# energy-harvesting-demoboard_v11.net
KiCad netlist of a schematic drawn in EAGLE
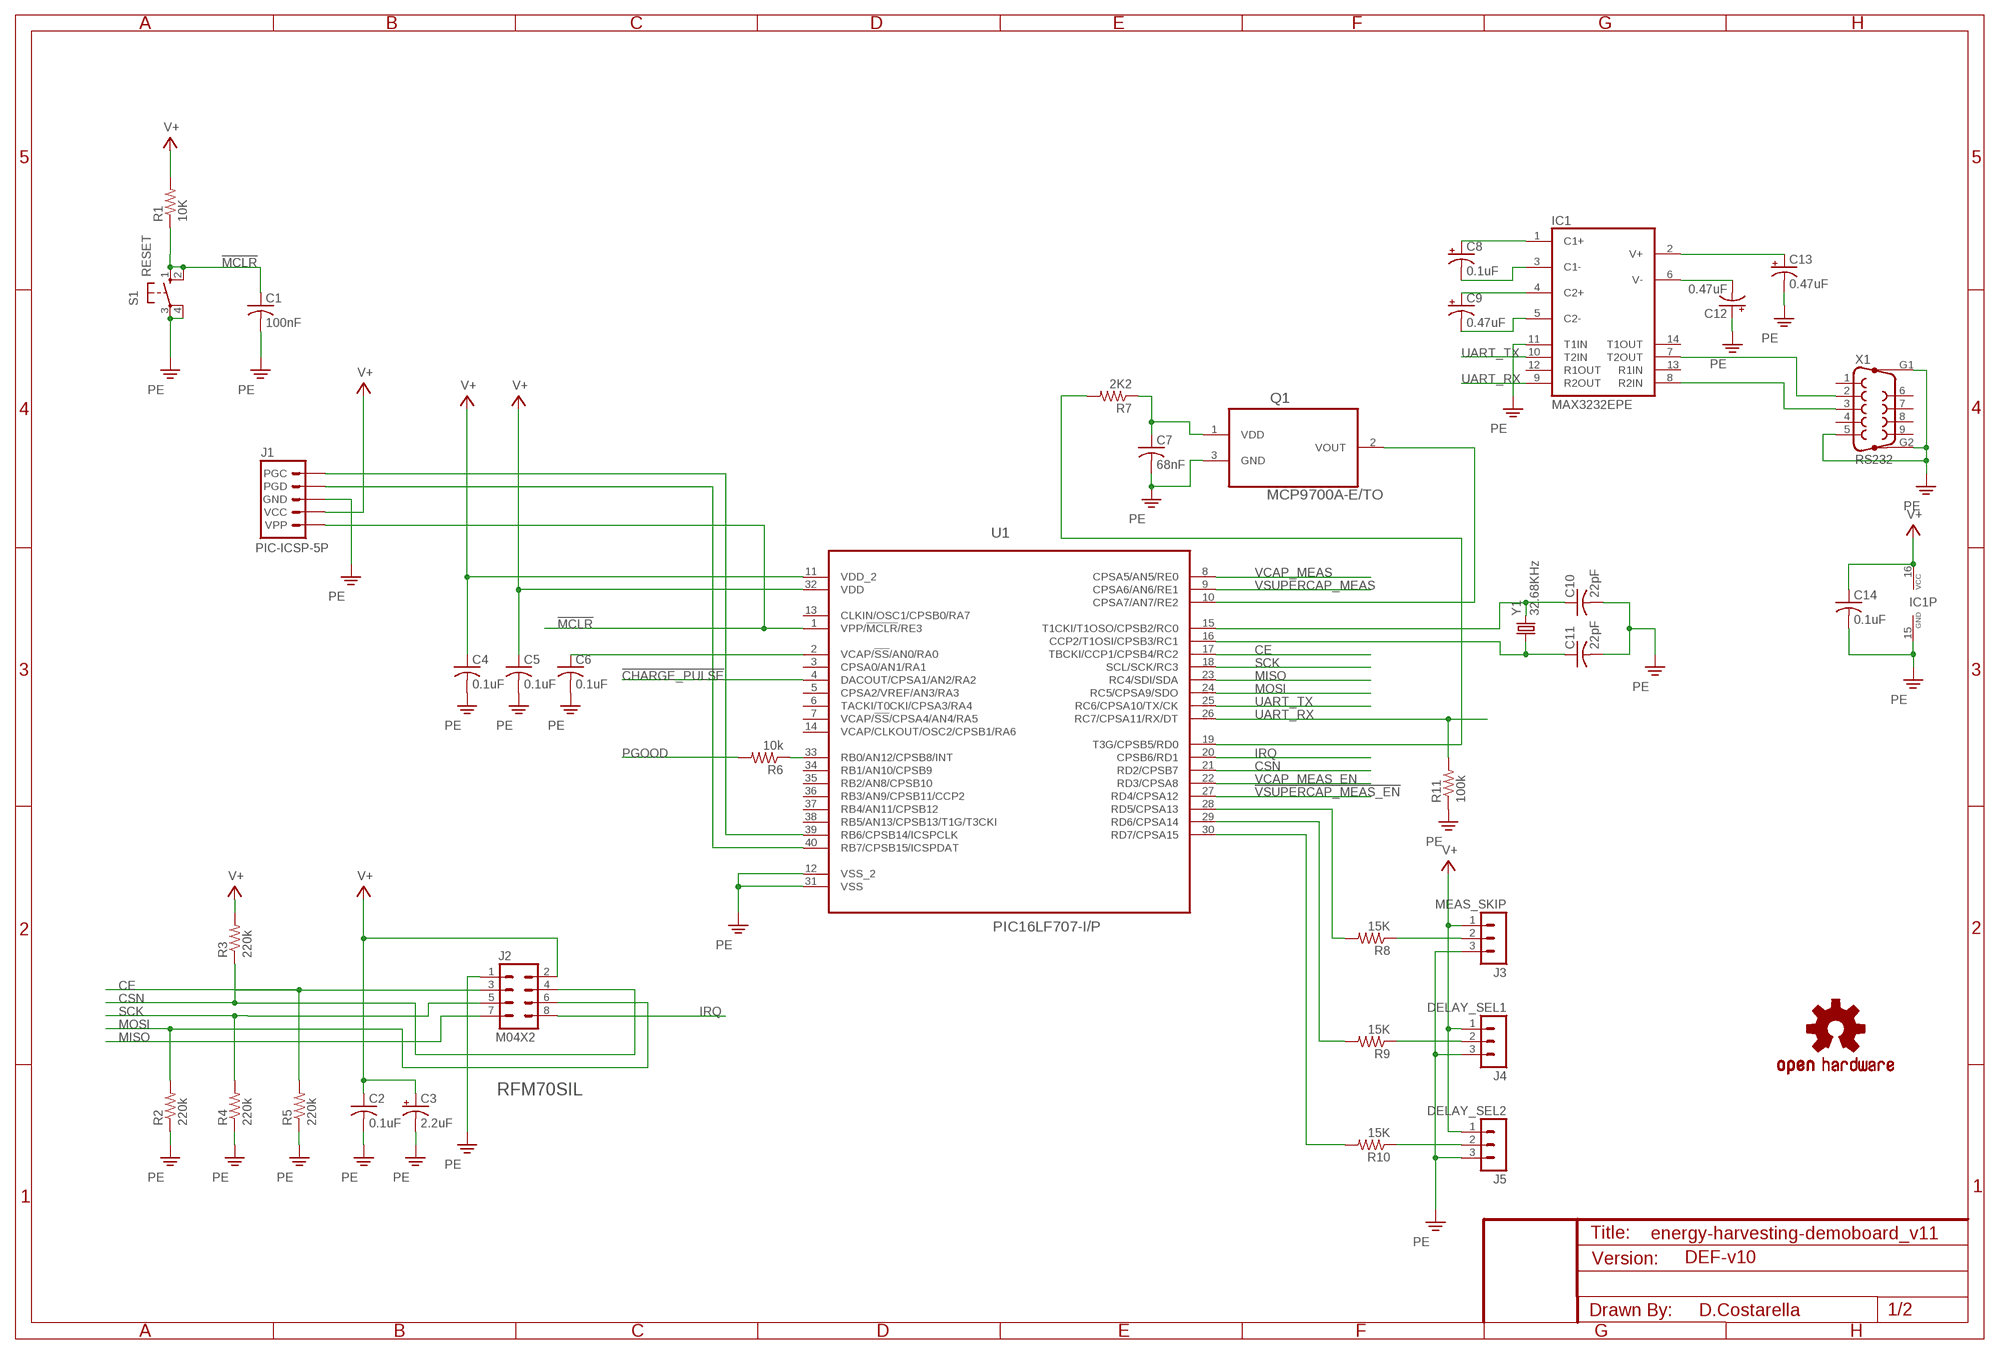
[diagram p0: schematic, sheet 1]
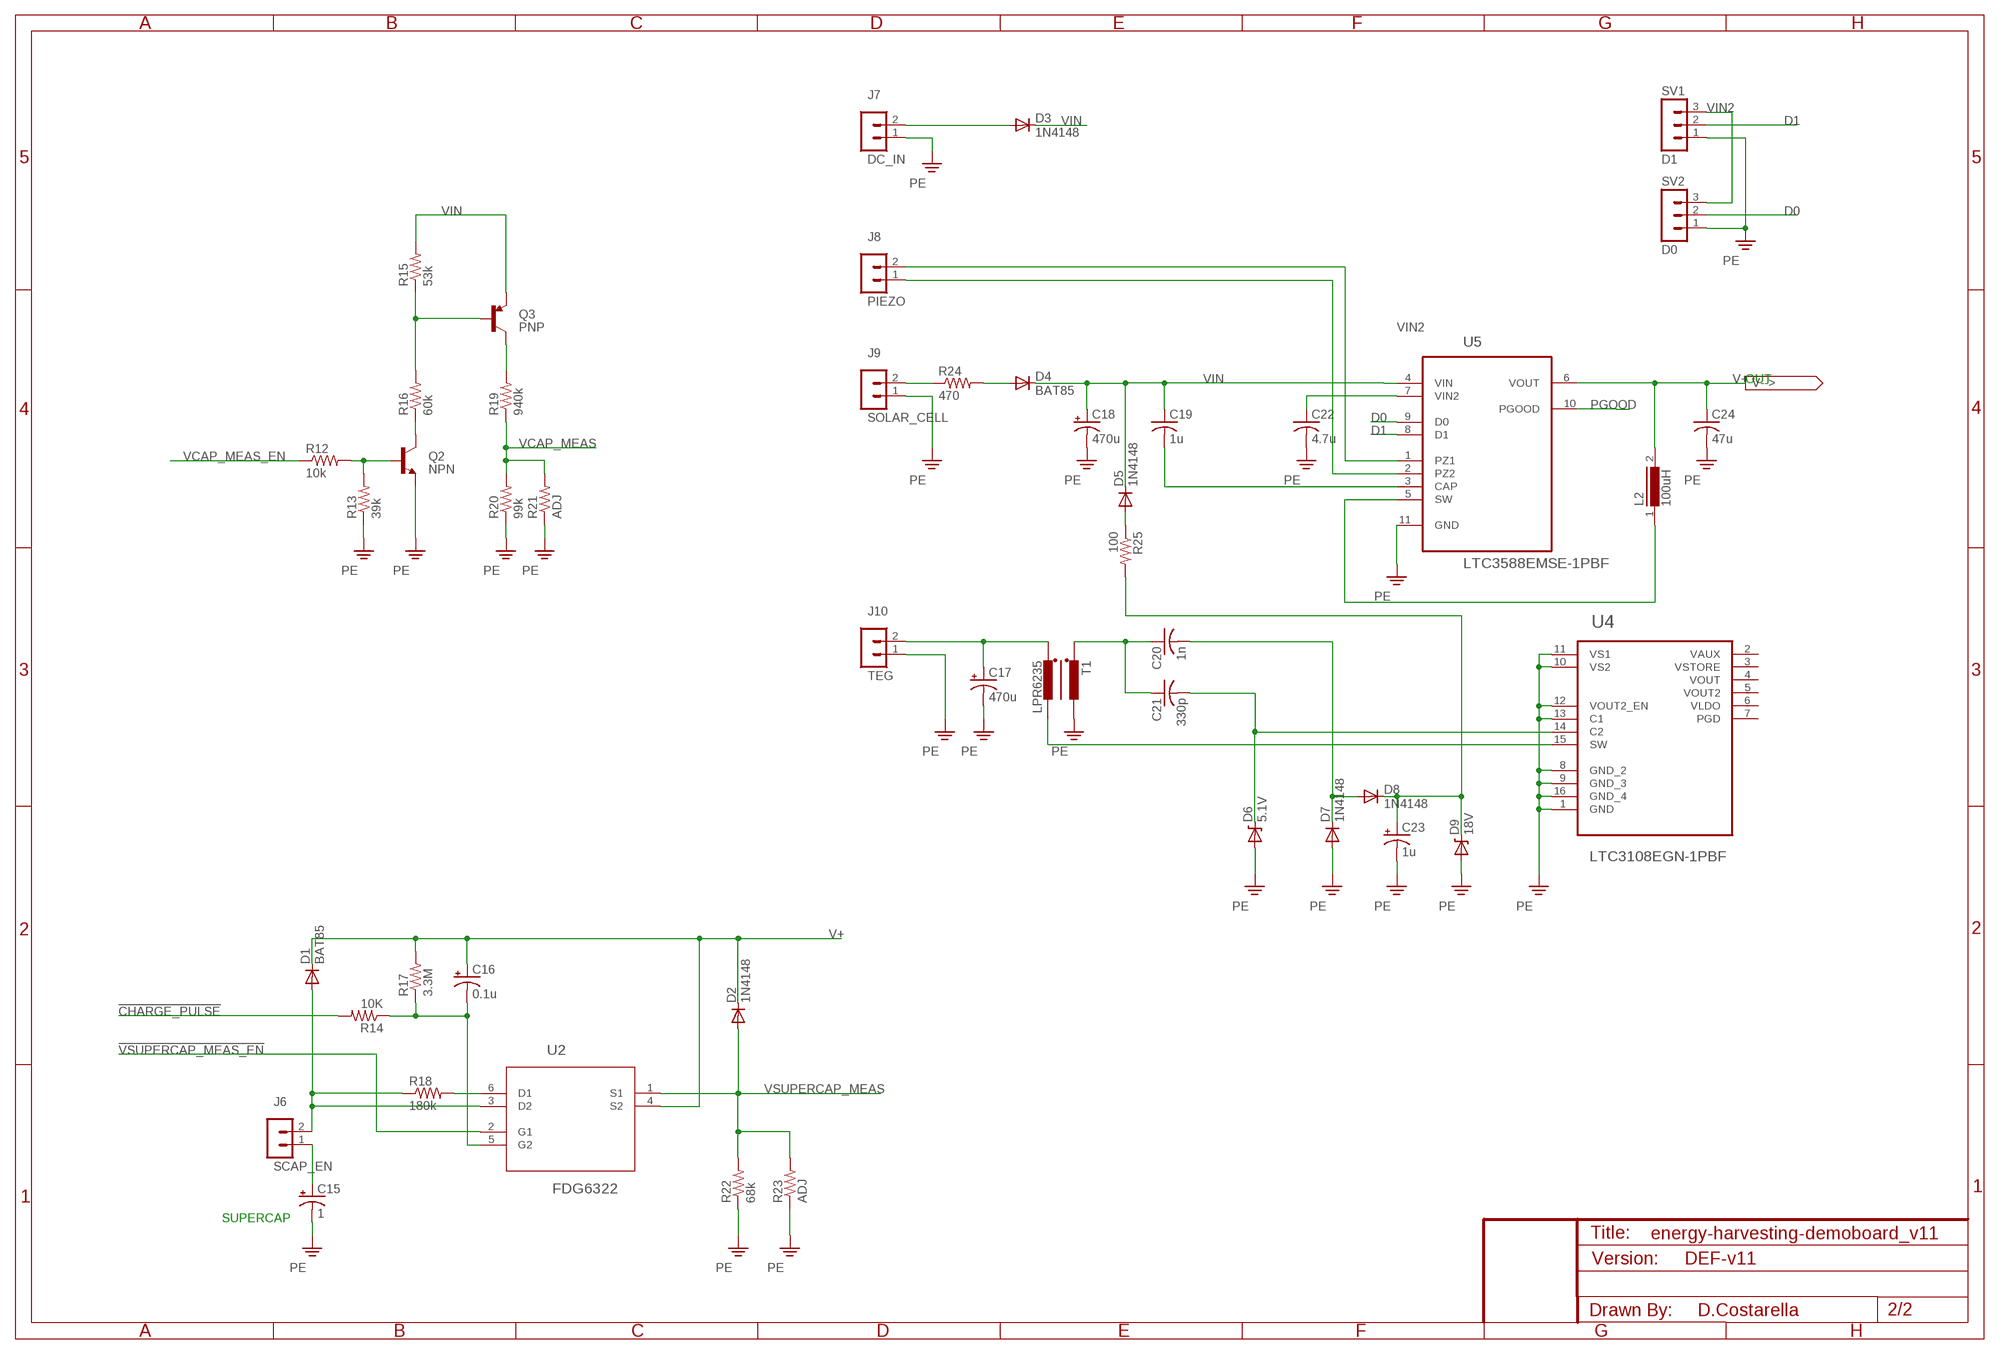
[diagram p1: schematic, sheet 2]

(export (version "E")
  (design (tool "Eeschema 10.0.6"))
  (components
    (comp (ref "C15")
      (value "1")
      (footprint "eagle-import:E5-8,5")
      (libsource (lib "eagle-import") (part "CPOL-USE5-8.5"))
    )
    (comp (ref "C16")
      (value "0.1u")
      (footprint "eagle-import:E2,5-5")
      (libsource (lib "eagle-import") (part "CPOL-USE2.5-5"))
    )
    (comp (ref "C17")
      (value "470u")
      (footprint "eagle-import:E5-10,5")
      (libsource (lib "eagle-import") (part "CPOL-USE5-10.5"))
    )
    (comp (ref "C18")
      (value "470u")
      (footprint "eagle-import:E5-10,5")
      (libsource (lib "eagle-import") (part "CPOL-USE5-10.5"))
    )
    (comp (ref "C19")
      (value "1u")
      (footprint "eagle-import:C050-035X075")
      (libsource (lib "eagle-import") (part "C-US050-035X075"))
    )
    (comp (ref "C20")
      (value "1n")
      (footprint "eagle-import:C050-030X075")
      (libsource (lib "eagle-import") (part "C-US050-030X075"))
    )
    (comp (ref "C21")
      (value "330p")
      (footprint "eagle-import:C050-030X075")
      (libsource (lib "eagle-import") (part "C-US050-030X075"))
    )
    (comp (ref "C22")
      (value "4.7u")
      (footprint "eagle-import:C025-024X044")
      (libsource (lib "eagle-import") (part "C-US025-024X044"))
    )
    (comp (ref "C23")
      (value "1u")
      (footprint "eagle-import:E2,5-6E")
      (libsource (lib "eagle-import") (part "CPOL-USE2,5-6E"))
    )
    (comp (ref "C24")
      (value "47u")
      (footprint "eagle-import:C050-025X075")
      (libsource (lib "eagle-import") (part "C-US050-025X075"))
    )
    (comp (ref "D1")
      (value "BAT85")
      (footprint "eagle-import:DIODE-1N4148")
      (libsource (lib "eagle-import") (part "DIODE1N4148"))
    )
    (comp (ref "D2")
      (value "1N4148")
      (footprint "eagle-import:DIODE-1N4148")
      (libsource (lib "eagle-import") (part "DIODE1N4148"))
    )
    (comp (ref "D3")
      (value "1N4148")
      (footprint "eagle-import:SMA-DIODE")
      (libsource (lib "eagle-import") (part "DIODESMA"))
    )
    (comp (ref "D4")
      (value "BAT85")
      (footprint "eagle-import:DIODE-1N4148")
      (libsource (lib "eagle-import") (part "DIODE1N4148"))
    )
    (comp (ref "D5")
      (value "1N4148")
      (footprint "eagle-import:SMA-DIODE")
      (libsource (lib "eagle-import") (part "DIODESMA"))
    )
    (comp (ref "D6")
      (value "5.1V")
      (footprint "eagle-import:DIODE-ZENER")
      (libsource (lib "eagle-import") (part "DIODE-ZENERPTH"))
    )
    (comp (ref "D7")
      (value "1N4148")
      (footprint "eagle-import:DIODE-1N4148")
      (libsource (lib "eagle-import") (part "DIODE1N4148"))
    )
    (comp (ref "D8")
      (value "1N4148")
      (footprint "eagle-import:DIODE-1N4148")
      (libsource (lib "eagle-import") (part "DIODE1N4148"))
    )
    (comp (ref "D9")
      (value "18V")
      (footprint "eagle-import:DIODE-ZENER")
      (libsource (lib "eagle-import") (part "DIODE-ZENERPTH"))
    )
    (comp (ref "J6")
      (value "SCAP_EN")
      (footprint "eagle-import:MA02-1")
      (libsource (lib "eagle-import") (part "MA02-1"))
    )
    (comp (ref "J7")
      (value "DC_IN")
      (footprint "eagle-import:MA02-1")
      (libsource (lib "eagle-import") (part "MA02-1"))
    )
    (comp (ref "J8")
      (value "PIEZO")
      (footprint "eagle-import:MA02-1")
      (libsource (lib "eagle-import") (part "MA02-1"))
    )
    (comp (ref "J9")
      (value "SOLAR_CELL")
      (footprint "eagle-import:MA02-1")
      (libsource (lib "eagle-import") (part "MA02-1"))
    )
    (comp (ref "J10")
      (value "TEG")
      (footprint "eagle-import:MA02-1")
      (libsource (lib "eagle-import") (part "MA02-1"))
    )
    (comp (ref "L2")
      (value "100uH")
      (footprint "eagle-import:DR125")
      (libsource (lib "eagle-import") (part "DR125"))
    )
    (comp (ref "Q2")
      (value "NPN")
      (footprint "eagle-import:TO-92")
      (libsource (lib "eagle-import") (part "TRANSISTOR_NPN_2PTH"))
    )
    (comp (ref "Q3")
      (value "PNP")
      (footprint "eagle-import:TO-92")
      (libsource (lib "eagle-import") (part "TRANSISTOR_PNPTO92"))
    )
    (comp (ref "R12")
      (value "10k")
      (footprint "eagle-import:AXIAL-0.4")
      (libsource (lib "eagle-import") (part "RESISTORPTH-1/4W"))
    )
    (comp (ref "R13")
      (value "39k")
      (footprint "eagle-import:AXIAL-0.4")
      (libsource (lib "eagle-import") (part "RESISTORPTH-1/4W"))
    )
    (comp (ref "R14")
      (value "10K")
      (footprint "eagle-import:AXIAL-0.4")
      (libsource (lib "eagle-import") (part "RESISTORPTH-1/4W"))
    )
    (comp (ref "R15")
      (value "53k")
      (footprint "eagle-import:AXIAL-0.4")
      (libsource (lib "eagle-import") (part "RESISTORPTH-1/4W"))
    )
    (comp (ref "R16")
      (value "60k")
      (footprint "eagle-import:AXIAL-0.4")
      (libsource (lib "eagle-import") (part "RESISTORPTH-1/4W"))
    )
    (comp (ref "R17")
      (value "3.3M")
      (footprint "eagle-import:AXIAL-0.4")
      (libsource (lib "eagle-import") (part "RESISTORPTH-1/4W"))
    )
    (comp (ref "R18")
      (value "180k")
      (footprint "eagle-import:AXIAL-0.4")
      (libsource (lib "eagle-import") (part "RESISTORPTH-1/4W"))
    )
    (comp (ref "R19")
      (value "940k")
      (footprint "eagle-import:AXIAL-0.4")
      (libsource (lib "eagle-import") (part "RESISTORPTH-1/4W"))
    )
    (comp (ref "R20")
      (value "99k")
      (footprint "eagle-import:AXIAL-0.4")
      (libsource (lib "eagle-import") (part "RESISTORPTH-1/4W"))
    )
    (comp (ref "R21")
      (value "ADJ")
      (footprint "eagle-import:AXIAL-0.4")
      (libsource (lib "eagle-import") (part "RESISTORPTH-1/4W"))
    )
    (comp (ref "R22")
      (value "68k")
      (footprint "eagle-import:AXIAL-0.4")
      (libsource (lib "eagle-import") (part "RESISTORPTH-1/4W"))
    )
    (comp (ref "R23")
      (value "ADJ")
      (footprint "eagle-import:AXIAL-0.4")
      (libsource (lib "eagle-import") (part "RESISTORPTH-1/4W"))
    )
    (comp (ref "R24")
      (value "470")
      (footprint "eagle-import:AXIAL-0.4")
      (libsource (lib "eagle-import") (part "RESISTORPTH-1/4W"))
    )
    (comp (ref "R25")
      (value "100")
      (footprint "eagle-import:AXIAL-0.4")
      (libsource (lib "eagle-import") (part "RESISTORPTH-1/4W"))
    )
    (comp (ref "SV1")
      (value "D1")
      (footprint "eagle-import:MA03-1")
      (libsource (lib "eagle-import") (part "MA03-1"))
    )
    (comp (ref "SV2")
      (value "D0")
      (footprint "eagle-import:MA03-1")
      (libsource (lib "eagle-import") (part "MA03-1"))
    )
    (comp (ref "T1")
      (value "LPR6235")
      (footprint "eagle-import:LPR6235")
      (libsource (lib "eagle-import") (part "LPR6235"))
    )
    (comp (ref "U2")
      (value "FDG6322")
      (footprint "eagle-import:SOT65P210X110-6N")
      (fields (field (name "MPN") "BSS138PS"))
      (libsource (lib "eagle-import") (part "BSS138PS"))
    )
    (comp (ref "U4")
      (value "LTC3108EGN-1PBF")
      (footprint "eagle-import:SOP63P600X175-16N")
      (fields (field (name "MPN") "LTC3108EGN-1#PBF"))
      (libsource (lib "eagle-import") (part "LTC3108EGN-1PBF"))
    )
    (comp (ref "U5")
      (value "LTC3588EMSE-1PBF")
      (footprint "eagle-import:SOP50P490X110-11N")
      (fields (field (name "MPN") "LTC3588EMSE-1#PBF"))
      (libsource (lib "eagle-import") (part "LTC3588EMSE-1PBF"))
    )
    (comp (ref "C1")
      (value "100nF")
      (footprint "eagle-import:C025-025X050")
      (libsource (lib "eagle-import") (part "C-US025-025X050"))
    )
    (comp (ref "C2")
      (value "0.1uF")
      (footprint "eagle-import:C050-025X075")
      (libsource (lib "eagle-import") (part "C-US050-025X075"))
    )
    (comp (ref "C3")
      (value "2.2uF")
      (footprint "eagle-import:E2,5-5")
      (libsource (lib "eagle-import") (part "CPOL-USE2.5-5"))
    )
    (comp (ref "C4")
      (value "0.1uF")
      (footprint "eagle-import:C050-025X075")
      (libsource (lib "eagle-import") (part "C-US050-025X075"))
    )
    (comp (ref "C5")
      (value "0.1uF")
      (footprint "eagle-import:C050-025X075")
      (libsource (lib "eagle-import") (part "C-US050-025X075"))
    )
    (comp (ref "C6")
      (value "0.1uF")
      (footprint "eagle-import:C050-025X075")
      (libsource (lib "eagle-import") (part "C-US050-025X075"))
    )
    (comp (ref "C7")
      (value "68nF")
      (footprint "eagle-import:C050-035X075")
      (libsource (lib "eagle-import") (part "C-US050-035X075"))
    )
    (comp (ref "C8")
      (value "0.1uF")
      (footprint "eagle-import:E2,5-5")
      (libsource (lib "eagle-import") (part "CPOL-USE2.5-5"))
    )
    (comp (ref "C9")
      (value "0.47uF")
      (footprint "eagle-import:E2,5-5")
      (libsource (lib "eagle-import") (part "CPOL-USE2.5-5"))
    )
    (comp (ref "C10")
      (value "22pF")
      (footprint "eagle-import:C025-025X050")
      (libsource (lib "eagle-import") (part "C-US025-025X050"))
    )
    (comp (ref "C11")
      (value "22pF")
      (footprint "eagle-import:C025-025X050")
      (libsource (lib "eagle-import") (part "C-US025-025X050"))
    )
    (comp (ref "C12")
      (value "0.47uF")
      (footprint "eagle-import:E2,5-5")
      (libsource (lib "eagle-import") (part "CPOL-USE2.5-5"))
    )
    (comp (ref "C13")
      (value "0.47uF")
      (footprint "eagle-import:E2,5-5")
      (libsource (lib "eagle-import") (part "CPOL-USE2.5-5"))
    )
    (comp (ref "C14")
      (value "0.1uF")
      (footprint "eagle-import:C050-030X075")
      (libsource (lib "eagle-import") (part "C-US050-030X075"))
    )
    (comp (ref "IC1")
      (value "MAX3232EPE")
      (footprint "eagle-import:DIL16")
      (fields (field (name "MPN") "MAX3232EPE+"))
      (libsource (lib "eagle-import") (part "MAX3232PEE"))
    )
    (comp (ref "J1")
      (value "PIC-ICSP-5P")
      (footprint "eagle-import:1X05")
      (libsource (lib "eagle-import") (part "PIC-ICSP-5P"))
    )
    (comp (ref "J2")
      (value "M04X2")
      (footprint "eagle-import:2X4")
      (libsource (lib "eagle-import") (part "M04X2"))
    )
    (comp (ref "J3")
      (value "MEAS_SKIP")
      (footprint "eagle-import:MA03-1")
      (libsource (lib "eagle-import") (part "MA03-1"))
    )
    (comp (ref "J4")
      (value "DELAY_SEL1")
      (footprint "eagle-import:MA03-1")
      (libsource (lib "eagle-import") (part "MA03-1"))
    )
    (comp (ref "J5")
      (value "DELAY_SEL2")
      (footprint "eagle-import:MA03-1")
      (libsource (lib "eagle-import") (part "MA03-1"))
    )
    (comp (ref "LOGO1")
      (value "OSHW-LOGOL")
      (footprint "eagle-import:OSHW-LOGO-L")
      (libsource (lib "eagle-import") (part "OSHW-LOGOL"))
    )
    (comp (ref "Q1")
      (value "MCP9700A-E/TO")
      (footprint "eagle-import:TO127P254X533-3")
      (libsource (lib "eagle-import") (part "MCP9700A-E/TO"))
    )
    (comp (ref "R1")
      (value "10K")
      (footprint "eagle-import:AXIAL-0.4")
      (libsource (lib "eagle-import") (part "RESISTORPTH-1/4W"))
    )
    (comp (ref "R2")
      (value "220k")
      (footprint "eagle-import:AXIAL-0.4")
      (libsource (lib "eagle-import") (part "RESISTORPTH-1/4W"))
    )
    (comp (ref "R3")
      (value "220k")
      (footprint "eagle-import:AXIAL-0.4")
      (libsource (lib "eagle-import") (part "RESISTORPTH-1/4W"))
    )
    (comp (ref "R4")
      (value "220k")
      (footprint "eagle-import:AXIAL-0.4")
      (libsource (lib "eagle-import") (part "RESISTORPTH-1/4W"))
    )
    (comp (ref "R5")
      (value "220k")
      (footprint "eagle-import:AXIAL-0.4")
      (libsource (lib "eagle-import") (part "RESISTORPTH-1/4W"))
    )
    (comp (ref "R6")
      (value "10k")
      (footprint "eagle-import:AXIAL-0.4")
      (libsource (lib "eagle-import") (part "RESISTORPTH-1/4W"))
    )
    (comp (ref "R7")
      (value "2K2")
      (footprint "eagle-import:AXIAL-0.4")
      (libsource (lib "eagle-import") (part "RESISTORPTH-1/4W"))
    )
    (comp (ref "R8")
      (value "15K")
      (footprint "eagle-import:AXIAL-0.4")
      (libsource (lib "eagle-import") (part "RESISTORPTH-1/4W"))
    )
    (comp (ref "R9")
      (value "15K")
      (footprint "eagle-import:AXIAL-0.4")
      (libsource (lib "eagle-import") (part "RESISTORPTH-1/4W"))
    )
    (comp (ref "R10")
      (value "15K")
      (footprint "eagle-import:AXIAL-0.4")
      (libsource (lib "eagle-import") (part "RESISTORPTH-1/4W"))
    )
    (comp (ref "R11")
      (value "100k")
      (footprint "eagle-import:AXIAL-0.4")
      (libsource (lib "eagle-import") (part "RESISTORPTH-1/4W"))
    )
    (comp (ref "S1")
      (value "RESET")
      (footprint "eagle-import:B3F-10XX")
      (fields (field (name "MPN") "B3F-1000"))
      (libsource (lib "eagle-import") (part "10-XX"))
    )
    (comp (ref "U1")
      (value "PIC16LF707-I/P")
      (footprint "eagle-import:DIP254P1524X635-40")
      (fields (field (name "MPN") "PIC16F707-I/P"))
      (libsource (lib "eagle-import") (part "PIC16F707-I/P"))
    )
    (comp (ref "X1")
      (value "RS232")
      (footprint "eagle-import:F09HP")
      (libsource (lib "eagle-import") (part "F09HP"))
    )
    (comp (ref "Y1")
      (value "32.68KHz")
      (footprint "eagle-import:TC26HEZ")
      (libsource (lib "eagle-import") (part "CRYSTALTC26H_EZ"))
    )
  )
  (nets
    (net (code "1") (name "CE") (class "Default")
      (node (ref "J2") (pin "3") (pinfunction "3_3") (pintype "passive"))
      (node (ref "R5") (pin "P$2") (pinfunction "2_P$2") (pintype "passive"))
      (node (ref "U1") (pin "17") (pinfunction "TBCKI/CCP1/CPSB4/RC2_17") (pintype "bidirectional"))
    )
    (net (code "2") (name "CSN") (class "Default")
      (node (ref "J2") (pin "4") (pinfunction "4_4") (pintype "passive"))
      (node (ref "R3") (pin "P$1") (pinfunction "1_P$1") (pintype "passive"))
      (node (ref "U1") (pin "21") (pinfunction "RD2/CPSB7_21") (pintype "bidirectional"))
    )
    (net (code "3") (name "D0") (class "Default")
      (node (ref "SV2") (pin "2") (pinfunction "2_2") (pintype "passive"))
      (node (ref "U5") (pin "9") (pinfunction "D0_9") (pintype "input"))
    )
    (net (code "4") (name "D1") (class "Default")
      (node (ref "SV1") (pin "2") (pinfunction "2_2") (pintype "passive"))
      (node (ref "U5") (pin "8") (pinfunction "D1_8") (pintype "input"))
    )
    (net (code "5") (name "IRQ") (class "Default")
      (node (ref "J2") (pin "8") (pinfunction "8_8") (pintype "passive"))
      (node (ref "U1") (pin "20") (pinfunction "CPSB6/RD1_20") (pintype "bidirectional"))
    )
    (net (code "6") (name "MISO") (class "Default")
      (node (ref "J2") (pin "7") (pinfunction "7_7") (pintype "passive"))
      (node (ref "U1") (pin "23") (pinfunction "RC4/SDI/SDA_23") (pintype "bidirectional"))
    )
    (net (code "7") (name "MOSI") (class "Default")
      (node (ref "J2") (pin "6") (pinfunction "6_6") (pintype "passive"))
      (node (ref "R2") (pin "P$2") (pinfunction "2_P$2") (pintype "passive"))
      (node (ref "U1") (pin "24") (pinfunction "RC5/CPSA9/SDO_24") (pintype "bidirectional"))
    )
    (net (code "8") (name "Net-(C15-Pad+)") (class "Default")
      (node (ref "C15") (pin "+") (pinfunction "+_+") (pintype "passive"))
      (node (ref "J6") (pin "1") (pinfunction "1_1") (pintype "passive"))
    )
    (net (code "9") (name "Net-(C20-Pad2)") (class "Default")
      (node (ref "C20") (pin "2") (pinfunction "2_2") (pintype "passive"))
      (node (ref "D7") (pin "C") (pinfunction "C_C") (pintype "passive"))
      (node (ref "D8") (pin "A") (pinfunction "A_A") (pintype "passive"))
    )
    (net (code "10") (name "Net-(D3-PadA)") (class "Default")
      (node (ref "D3") (pin "A") (pinfunction "A_A") (pintype "passive"))
      (node (ref "J7") (pin "2") (pinfunction "2_2") (pintype "passive"))
    )
    (net (code "11") (name "Net-(D6-C)") (class "Default")
      (node (ref "C21") (pin "2") (pinfunction "2_2") (pintype "passive"))
      (node (ref "D6") (pin "P$1") (pinfunction "C_P$1") (pintype "passive"))
      (node (ref "U4") (pin "14") (pinfunction "C2_14") (pintype "input"))
    )
    (net (code "12") (name "Net-(D9-C)") (class "Default")
      (node (ref "C23") (pin "+") (pinfunction "+_+") (pintype "passive"))
      (node (ref "D8") (pin "C") (pinfunction "C_C") (pintype "passive"))
      (node (ref "D9") (pin "P$1") (pinfunction "C_P$1") (pintype "passive"))
      (node (ref "R25") (pin "P$2") (pinfunction "2_P$2") (pintype "passive"))
    )
    (net (code "13") (name "Net-(IC1A-C1+)") (class "Default")
      (node (ref "C8") (pin "+") (pinfunction "+_+") (pintype "passive"))
      (node (ref "IC1") (pin "1") (pinfunction "C1+_1") (pintype "bidirectional"))
    )
    (net (code "14") (name "Net-(IC1A-C1-)") (class "Default")
      (node (ref "C8") (pin "-") (pinfunction "-_-") (pintype "passive"))
      (node (ref "IC1") (pin "3") (pinfunction "C1-_3") (pintype "bidirectional"))
    )
    (net (code "15") (name "Net-(IC1A-C2+)") (class "Default")
      (node (ref "C9") (pin "+") (pinfunction "+_+") (pintype "passive"))
      (node (ref "IC1") (pin "4") (pinfunction "C2+_4") (pintype "bidirectional"))
    )
    (net (code "16") (name "Net-(IC1A-C2-)") (class "Default")
      (node (ref "C9") (pin "-") (pinfunction "-_-") (pintype "passive"))
      (node (ref "IC1") (pin "5") (pinfunction "C2-_5") (pintype "bidirectional"))
    )
    (net (code "17") (name "Net-(IC1A-R2IN)") (class "Default")
      (node (ref "IC1") (pin "8") (pinfunction "R2IN_8") (pintype "input"))
      (node (ref "X1") (pin "3") (pinfunction "3_3") (pintype "passive"))
    )
    (net (code "18") (name "Net-(IC1A-T2OUT)") (class "Default")
      (node (ref "IC1") (pin "7") (pinfunction "T2OUT_7") (pintype "output"))
      (node (ref "X1") (pin "2") (pinfunction "2_2") (pintype "passive"))
    )
    (net (code "19") (name "Net-(IC1A-V+)") (class "Default")
      (node (ref "C13") (pin "+") (pinfunction "+_+") (pintype "passive"))
      (node (ref "IC1") (pin "2") (pinfunction "V+_2") (pintype "bidirectional"))
    )
    (net (code "20") (name "Net-(IC1A-V-)") (class "Default")
      (node (ref "C12") (pin "-") (pinfunction "-_-") (pintype "passive"))
      (node (ref "IC1") (pin "6") (pinfunction "V-_6") (pintype "bidirectional"))
    )
    (net (code "21") (name "Net-(J1-PGC)") (class "Default")
      (node (ref "J1") (pin "5") (pinfunction "PGC_5") (pintype "passive"))
      (node (ref "U1") (pin "39") (pinfunction "RB6/CPSB14/ICSPCLK_39") (pintype "bidirectional"))
    )
    (net (code "22") (name "Net-(J1-PGD)") (class "Default")
      (node (ref "J1") (pin "4") (pinfunction "PGD_4") (pintype "passive"))
      (node (ref "U1") (pin "40") (pinfunction "RB7/CPSB15/ICSPDAT_40") (pintype "bidirectional"))
    )
    (net (code "23") (name "Net-(Q1-VDD)") (class "Default")
      (node (ref "C7") (pin "1") (pinfunction "1_1") (pintype "passive"))
      (node (ref "Q1") (pin "1") (pinfunction "VDD_1") (pintype "power_in"))
      (node (ref "R7") (pin "P$1") (pinfunction "1_P$1") (pintype "passive"))
    )
    (net (code "24") (name "Net-(Q1-VOUT)") (class "Default")
      (node (ref "Q1") (pin "2") (pinfunction "VOUT_2") (pintype "output"))
      (node (ref "U1") (pin "10") (pinfunction "CPSA7/AN7/RE2_10") (pintype "bidirectional"))
    )
    (net (code "25") (name "Net-(Q2-B)") (class "Default")
      (node (ref "Q2") (pin "2") (pinfunction "B_2") (pintype "passive"))
      (node (ref "R12") (pin "P$2") (pinfunction "2_P$2") (pintype "passive"))
      (node (ref "R13") (pin "P$2") (pinfunction "2_P$2") (pintype "passive"))
    )
    (net (code "26") (name "Net-(Q2-C)") (class "Default")
      (node (ref "Q2") (pin "1") (pinfunction "C_1") (pintype "passive"))
      (node (ref "R16") (pin "P$1") (pinfunction "1_P$1") (pintype "passive"))
    )
    (net (code "27") (name "Net-(Q3-B)") (class "Default")
      (node (ref "Q3") (pin "2") (pinfunction "B_2") (pintype "passive"))
      (node (ref "R15") (pin "P$1") (pinfunction "1_P$1") (pintype "passive"))
      (node (ref "R16") (pin "P$2") (pinfunction "2_P$2") (pintype "passive"))
    )
    (net (code "28") (name "Net-(Q3-C)") (class "Default")
      (node (ref "Q3") (pin "3") (pinfunction "C_3") (pintype "passive"))
      (node (ref "R19") (pin "P$2") (pinfunction "2_P$2") (pintype "passive"))
    )
    (net (code "29") (name "Net-(R6-1)") (class "Default")
      (node (ref "R6") (pin "P$1") (pinfunction "1_P$1") (pintype "passive"))
      (node (ref "U1") (pin "33") (pinfunction "RB0/AN12/CPSB8/INT_33") (pintype "bidirectional"))
    )
    (net (code "30") (name "Net-(R7-2)") (class "Default")
      (node (ref "R7") (pin "P$2") (pinfunction "2_P$2") (pintype "passive"))
      (node (ref "U1") (pin "19") (pinfunction "T3G/CPSB5/RD0_19") (pintype "bidirectional"))
    )
    (net (code "31") (name "Net-(R8-1)") (class "Default")
      (node (ref "J3") (pin "2") (pinfunction "2_2") (pintype "passive"))
      (node (ref "R8") (pin "P$1") (pinfunction "1_P$1") (pintype "passive"))
    )
    (net (code "32") (name "Net-(R8-2)") (class "Default")
      (node (ref "R8") (pin "P$2") (pinfunction "2_P$2") (pintype "passive"))
      (node (ref "U1") (pin "28") (pinfunction "RD5/CPSA13_28") (pintype "bidirectional"))
    )
    (net (code "33") (name "Net-(R9-1)") (class "Default")
      (node (ref "J4") (pin "2") (pinfunction "2_2") (pintype "passive"))
      (node (ref "R9") (pin "P$1") (pinfunction "1_P$1") (pintype "passive"))
    )
    (net (code "34") (name "Net-(R9-2)") (class "Default")
      (node (ref "R9") (pin "P$2") (pinfunction "2_P$2") (pintype "passive"))
      (node (ref "U1") (pin "29") (pinfunction "RD6/CPSA14_29") (pintype "bidirectional"))
    )
    (net (code "35") (name "Net-(R10-1)") (class "Default")
      (node (ref "J5") (pin "2") (pinfunction "2_2") (pintype "passive"))
      (node (ref "R10") (pin "P$1") (pinfunction "1_P$1") (pintype "passive"))
    )
    (net (code "36") (name "Net-(R10-2)") (class "Default")
      (node (ref "R10") (pin "P$2") (pinfunction "2_P$2") (pintype "passive"))
      (node (ref "U1") (pin "30") (pinfunction "RD7/CPSA15_30") (pintype "bidirectional"))
    )
    (net (code "37") (name "Net-(R14-1)") (class "Default")
      (node (ref "C16") (pin "-") (pinfunction "-_-") (pintype "passive"))
      (node (ref "R14") (pin "P$1") (pinfunction "1_P$1") (pintype "passive"))
      (node (ref "R17") (pin "P$1") (pinfunction "1_P$1") (pintype "passive"))
      (node (ref "U2") (pin "5") (pinfunction "G2_5") (pintype "input"))
    )
    (net (code "38") (name "Net-(R18-1)") (class "Default")
      (node (ref "D1") (pin "A") (pinfunction "A_A") (pintype "passive"))
      (node (ref "J6") (pin "2") (pinfunction "2_2") (pintype "passive"))
      (node (ref "R18") (pin "P$1") (pinfunction "1_P$1") (pintype "passive"))
      (node (ref "U2") (pin "3") (pinfunction "D2_3") (pintype "input"))
    )
    (net (code "39") (name "Net-(R18-2)") (class "Default")
      (node (ref "R18") (pin "P$2") (pinfunction "2_P$2") (pintype "passive"))
      (node (ref "U2") (pin "6") (pinfunction "D1_6") (pintype "input"))
    )
    (net (code "40") (name "Net-(R24-1)") (class "Default")
      (node (ref "J9") (pin "2") (pinfunction "2_2") (pintype "passive"))
      (node (ref "R24") (pin "P$1") (pinfunction "1_P$1") (pintype "passive"))
    )
    (net (code "41") (name "Net-(R24-2)") (class "Default")
      (node (ref "D4") (pin "A") (pinfunction "A_A") (pintype "passive"))
      (node (ref "R24") (pin "P$2") (pinfunction "2_P$2") (pintype "passive"))
    )
    (net (code "42") (name "Net-(R25-1)") (class "Default")
      (node (ref "D5") (pin "A") (pinfunction "A_A") (pintype "passive"))
      (node (ref "R25") (pin "P$1") (pinfunction "1_P$1") (pintype "passive"))
    )
    (net (code "43") (name "Net-(T1-1)") (class "Default")
      (node (ref "C17") (pin "+") (pinfunction "+_+") (pintype "passive"))
      (node (ref "J10") (pin "2") (pinfunction "2_2") (pintype "passive"))
      (node (ref "T1") (pin "P$1") (pinfunction "1_P$1") (pintype "passive"))
    )
    (net (code "44") (name "Net-(T1-2)") (class "Default")
      (node (ref "T1") (pin "P$2") (pinfunction "2_P$2") (pintype "passive"))
      (node (ref "U4") (pin "15") (pinfunction "SW_15") (pintype "passive"))
    )
    (net (code "45") (name "Net-(T1-4)") (class "Default")
      (node (ref "C20") (pin "1") (pinfunction "1_1") (pintype "passive"))
      (node (ref "C21") (pin "1") (pinfunction "1_1") (pintype "passive"))
      (node (ref "T1") (pin "P$4") (pinfunction "4_P$4") (pintype "passive"))
    )
    (net (code "46") (name "Net-(U1-CCP2{slash}T1OSI{slash}CPSB3{slash}RC1)") (class "Default")
      (node (ref "C11") (pin "1") (pinfunction "1_1") (pintype "passive"))
      (node (ref "U1") (pin "16") (pinfunction "CCP2/T1OSI/CPSB3/RC1_16") (pintype "bidirectional"))
      (node (ref "Y1") (pin "1") (pinfunction "1_1") (pintype "passive"))
    )
    (net (code "47") (name "Net-(U1-T1CKI{slash}T1OSO{slash}CPSB2{slash}RC0)") (class "Default")
      (node (ref "C10") (pin "1") (pinfunction "1_1") (pintype "passive"))
      (node (ref "U1") (pin "15") (pinfunction "T1CKI/T1OSO/CPSB2/RC0_15") (pintype "bidirectional"))
      (node (ref "Y1") (pin "2") (pinfunction "2_2") (pintype "passive"))
    )
    (net (code "48") (name "Net-(U1-VCAP{slash}~{SS}{slash}AN0{slash}RA0)") (class "Default")
      (node (ref "C6") (pin "1") (pinfunction "1_1") (pintype "passive"))
      (node (ref "U1") (pin "2") (pinfunction "VCAP/~{SS}/AN0/RA0_2") (pintype "bidirectional"))
    )
    (net (code "49") (name "Net-(U5-CAP)") (class "Default")
      (node (ref "C19") (pin "2") (pinfunction "2_2") (pintype "passive"))
      (node (ref "U5") (pin "3") (pinfunction "CAP_3") (pintype "passive"))
    )
    (net (code "50") (name "Net-(U5-PZ1)") (class "Default")
      (node (ref "J8") (pin "2") (pinfunction "2_2") (pintype "passive"))
      (node (ref "U5") (pin "1") (pinfunction "PZ1_1") (pintype "input"))
    )
    (net (code "51") (name "Net-(U5-PZ2)") (class "Default")
      (node (ref "J8") (pin "1") (pinfunction "1_1") (pintype "passive"))
      (node (ref "U5") (pin "2") (pinfunction "PZ2_2") (pintype "input"))
    )
    (net (code "52") (name "Net-(U5-SW)") (class "Default")
      (node (ref "L2") (pin "1") (pinfunction "1_1") (pintype "passive"))
      (node (ref "U5") (pin "5") (pinfunction "SW_5") (pintype "passive"))
    )
    (net (code "53") (name "PE") (class "Default")
      (node (ref "C1") (pin "2") (pinfunction "2_2") (pintype "passive"))
      (node (ref "C10") (pin "2") (pinfunction "2_2") (pintype "passive"))
      (node (ref "C11") (pin "2") (pinfunction "2_2") (pintype "passive"))
      (node (ref "C12") (pin "+") (pinfunction "+_+") (pintype "passive"))
      (node (ref "C13") (pin "-") (pinfunction "-_-") (pintype "passive"))
      (node (ref "C14") (pin "2") (pinfunction "2_2") (pintype "passive"))
      (node (ref "C15") (pin "-") (pinfunction "-_-") (pintype "passive"))
      (node (ref "C17") (pin "-") (pinfunction "-_-") (pintype "passive"))
      (node (ref "C18") (pin "-") (pinfunction "-_-") (pintype "passive"))
      (node (ref "C2") (pin "2") (pinfunction "2_2") (pintype "passive"))
      (node (ref "C22") (pin "2") (pinfunction "2_2") (pintype "passive"))
      (node (ref "C23") (pin "-") (pinfunction "-_-") (pintype "passive"))
      (node (ref "C24") (pin "2") (pinfunction "2_2") (pintype "passive"))
      (node (ref "C3") (pin "-") (pinfunction "-_-") (pintype "passive"))
      (node (ref "C4") (pin "2") (pinfunction "2_2") (pintype "passive"))
      (node (ref "C5") (pin "2") (pinfunction "2_2") (pintype "passive"))
      (node (ref "C6") (pin "2") (pinfunction "2_2") (pintype "passive"))
      (node (ref "C7") (pin "2") (pinfunction "2_2") (pintype "passive"))
      (node (ref "D6") (pin "P$2") (pinfunction "A_P$2") (pintype "passive"))
      (node (ref "D7") (pin "A") (pinfunction "A_A") (pintype "passive"))
      (node (ref "D9") (pin "P$2") (pinfunction "A_P$2") (pintype "passive"))
      (node (ref "IC1") (pin "11") (pinfunction "T1IN_11") (pintype "input"))
      (node (ref "IC1") (pin "15") (pinfunction "GND_15") (pintype "power_in"))
      (node (ref "J1") (pin "3") (pinfunction "GND_3") (pintype "passive"))
      (node (ref "J10") (pin "1") (pinfunction "1_1") (pintype "passive"))
      (node (ref "J2") (pin "1") (pinfunction "1_1") (pintype "passive"))
      (node (ref "J3") (pin "3") (pinfunction "3_3") (pintype "passive"))
      (node (ref "J4") (pin "3") (pinfunction "3_3") (pintype "passive"))
      (node (ref "J5") (pin "3") (pinfunction "3_3") (pintype "passive"))
      (node (ref "J7") (pin "1") (pinfunction "1_1") (pintype "passive"))
      (node (ref "J9") (pin "1") (pinfunction "1_1") (pintype "passive"))
      (node (ref "Q1") (pin "3") (pinfunction "GND_3") (pintype "passive"))
      (node (ref "Q2") (pin "3") (pinfunction "E_3") (pintype "passive"))
      (node (ref "R11") (pin "P$1") (pinfunction "1_P$1") (pintype "passive"))
      (node (ref "R13") (pin "P$1") (pinfunction "1_P$1") (pintype "passive"))
      (node (ref "R2") (pin "P$1") (pinfunction "1_P$1") (pintype "passive"))
      (node (ref "R20") (pin "P$1") (pinfunction "1_P$1") (pintype "passive"))
      (node (ref "R21") (pin "P$1") (pinfunction "1_P$1") (pintype "passive"))
      (node (ref "R22") (pin "P$1") (pinfunction "1_P$1") (pintype "passive"))
      (node (ref "R23") (pin "P$1") (pinfunction "1_P$1") (pintype "passive"))
      (node (ref "R4") (pin "P$1") (pinfunction "1_P$1") (pintype "passive"))
      (node (ref "R5") (pin "P$1") (pinfunction "1_P$1") (pintype "passive"))
      (node (ref "S1") (pin "3") (pinfunction "P_3") (pintype "passive"))
      (node (ref "S1") (pin "4") (pinfunction "P1_4") (pintype "passive"))
      (node (ref "SV1") (pin "1") (pinfunction "1_1") (pintype "passive"))
      (node (ref "SV2") (pin "1") (pinfunction "1_1") (pintype "passive"))
      (node (ref "T1") (pin "P$3") (pinfunction "3_P$3") (pintype "passive"))
      (node (ref "U1") (pin "12") (pinfunction "VSS_2_12") (pintype "passive"))
      (node (ref "U1") (pin "31") (pinfunction "VSS_31") (pintype "passive"))
      (node (ref "U4") (pin "1") (pinfunction "GND_1") (pintype "passive"))
      (node (ref "U4") (pin "10") (pinfunction "VS2_10") (pintype "input"))
      (node (ref "U4") (pin "11") (pinfunction "VS1_11") (pintype "input"))
      (node (ref "U4") (pin "12") (pinfunction "VOUT2_EN_12") (pintype "input"))
      (node (ref "U4") (pin "13") (pinfunction "C1_13") (pintype "input"))
      (node (ref "U4") (pin "16") (pinfunction "GND_4_16") (pintype "passive"))
      (node (ref "U4") (pin "8") (pinfunction "GND_2_8") (pintype "passive"))
      (node (ref "U4") (pin "9") (pinfunction "GND_3_9") (pintype "passive"))
      (node (ref "U5") (pin "11") (pinfunction "GND_11") (pintype "passive"))
      (node (ref "X1") (pin "5") (pinfunction "5_5") (pintype "passive"))
      (node (ref "X1") (pin "G1") (pinfunction "G1_G1") (pintype "passive"))
      (node (ref "X1") (pin "G2") (pinfunction "G2_G2") (pintype "passive"))
    )
    (net (code "54") (name "PGOOD") (class "Default")
      (node (ref "R6") (pin "P$2") (pinfunction "2_P$2") (pintype "passive"))
      (node (ref "U5") (pin "10") (pinfunction "PGOOD_10") (pintype "output"))
    )
    (net (code "55") (name "SCK") (class "Default")
      (node (ref "J2") (pin "5") (pinfunction "5_5") (pintype "passive"))
      (node (ref "R4") (pin "P$2") (pinfunction "2_P$2") (pintype "passive"))
      (node (ref "U1") (pin "18") (pinfunction "SCL/SCK/RC3_18") (pintype "bidirectional"))
    )
    (net (code "56") (name "UART_RX") (class "Default")
      (node (ref "IC1") (pin "9") (pinfunction "R2OUT_9") (pintype "output"))
      (node (ref "R11") (pin "P$2") (pinfunction "2_P$2") (pintype "passive"))
      (node (ref "U1") (pin "26") (pinfunction "RC7/CPSA11/RX/DT_26") (pintype "bidirectional"))
    )
    (net (code "57") (name "UART_TX") (class "Default")
      (node (ref "IC1") (pin "10") (pinfunction "T2IN_10") (pintype "input"))
      (node (ref "U1") (pin "25") (pinfunction "RC6/CPSA10/TX/CK_25") (pintype "bidirectional"))
    )
    (net (code "58") (name "V+") (class "Default")
      (node (ref "C14") (pin "1") (pinfunction "1_1") (pintype "passive"))
      (node (ref "C16") (pin "+") (pinfunction "+_+") (pintype "passive"))
      (node (ref "C2") (pin "1") (pinfunction "1_1") (pintype "passive"))
      (node (ref "C24") (pin "1") (pinfunction "1_1") (pintype "passive"))
      (node (ref "C3") (pin "+") (pinfunction "+_+") (pintype "passive"))
      (node (ref "C4") (pin "1") (pinfunction "1_1") (pintype "passive"))
      (node (ref "C5") (pin "1") (pinfunction "1_1") (pintype "passive"))
      (node (ref "D1") (pin "C") (pinfunction "C_C") (pintype "passive"))
      (node (ref "D2") (pin "C") (pinfunction "C_C") (pintype "passive"))
      (node (ref "IC1") (pin "16") (pinfunction "VCC_16") (pintype "power_in"))
      (node (ref "J1") (pin "2") (pinfunction "VCC_2") (pintype "passive"))
      (node (ref "J2") (pin "2") (pinfunction "2_2") (pintype "passive"))
      (node (ref "J3") (pin "1") (pinfunction "1_1") (pintype "passive"))
      (node (ref "J4") (pin "1") (pinfunction "1_1") (pintype "passive"))
      (node (ref "J5") (pin "1") (pinfunction "1_1") (pintype "passive"))
      (node (ref "L2") (pin "2") (pinfunction "2_2") (pintype "passive"))
      (node (ref "R1") (pin "P$2") (pinfunction "2_P$2") (pintype "passive"))
      (node (ref "R17") (pin "P$2") (pinfunction "2_P$2") (pintype "passive"))
      (node (ref "R3") (pin "P$2") (pinfunction "2_P$2") (pintype "passive"))
      (node (ref "U1") (pin "11") (pinfunction "VDD_2_11") (pintype "power_in"))
      (node (ref "U1") (pin "32") (pinfunction "VDD_32") (pintype "power_in"))
      (node (ref "U2") (pin "4") (pinfunction "S2_4") (pintype "output"))
      (node (ref "U5") (pin "6") (pinfunction "VOUT_6") (pintype "output"))
    )
    (net (code "59") (name "VCAP_MEAS") (class "Default")
      (node (ref "R19") (pin "P$1") (pinfunction "1_P$1") (pintype "passive"))
      (node (ref "R20") (pin "P$2") (pinfunction "2_P$2") (pintype "passive"))
      (node (ref "R21") (pin "P$2") (pinfunction "2_P$2") (pintype "passive"))
      (node (ref "U1") (pin "8") (pinfunction "CPSA5/AN5/RE0_8") (pintype "bidirectional"))
    )
    (net (code "60") (name "VCAP_MEAS_EN") (class "Default")
      (node (ref "R12") (pin "P$1") (pinfunction "1_P$1") (pintype "passive"))
      (node (ref "U1") (pin "22") (pinfunction "RD3/CPSA8_22") (pintype "bidirectional"))
    )
    (net (code "61") (name "VIN") (class "Default")
      (node (ref "C18") (pin "+") (pinfunction "+_+") (pintype "passive"))
      (node (ref "C19") (pin "1") (pinfunction "1_1") (pintype "passive"))
      (node (ref "D3") (pin "C") (pinfunction "C_C") (pintype "passive"))
      (node (ref "D4") (pin "C") (pinfunction "C_C") (pintype "passive"))
      (node (ref "D5") (pin "C") (pinfunction "C_C") (pintype "passive"))
      (node (ref "Q3") (pin "1") (pinfunction "E_1") (pintype "passive"))
      (node (ref "R15") (pin "P$2") (pinfunction "2_P$2") (pintype "passive"))
      (node (ref "U5") (pin "4") (pinfunction "VIN_4") (pintype "power_in"))
    )
    (net (code "62") (name "VIN2") (class "Default")
      (node (ref "C22") (pin "1") (pinfunction "1_1") (pintype "passive"))
      (node (ref "SV1") (pin "3") (pinfunction "3_3") (pintype "passive"))
      (node (ref "SV2") (pin "3") (pinfunction "3_3") (pintype "passive"))
      (node (ref "U5") (pin "7") (pinfunction "VIN2_7") (pintype "power_in"))
    )
    (net (code "63") (name "VSUPERCAP_MEAS") (class "Default")
      (node (ref "D2") (pin "A") (pinfunction "A_A") (pintype "passive"))
      (node (ref "R22") (pin "P$2") (pinfunction "2_P$2") (pintype "passive"))
      (node (ref "R23") (pin "P$2") (pinfunction "2_P$2") (pintype "passive"))
      (node (ref "U1") (pin "9") (pinfunction "CPSA6/AN6/RE1_9") (pintype "bidirectional"))
      (node (ref "U2") (pin "1") (pinfunction "S1_1") (pintype "output"))
    )
    (net (code "64") (name "unconnected-(IC1A-R1IN-Pad13)") (class "Default")
      (node (ref "IC1") (pin "13") (pinfunction "R1IN_13") (pintype "input"))
    )
    (net (code "65") (name "unconnected-(IC1A-R1OUT-Pad12)") (class "Default")
      (node (ref "IC1") (pin "12") (pinfunction "R1OUT_12") (pintype "output"))
    )
    (net (code "66") (name "unconnected-(IC1A-T1OUT-Pad14)") (class "Default")
      (node (ref "IC1") (pin "14") (pinfunction "T1OUT_14") (pintype "output"))
    )
    (net (code "67") (name "unconnected-(U1-CLKIN{slash}OSC1{slash}CPSB0{slash}RA7-Pad13)") (class "Default")
      (node (ref "U1") (pin "13") (pinfunction "CLKIN/OSC1/CPSB0/RA7_13") (pintype "input"))
    )
    (net (code "68") (name "unconnected-(U1-CPSA0{slash}AN1{slash}RA1-Pad3)") (class "Default")
      (node (ref "U1") (pin "3") (pinfunction "CPSA0/AN1/RA1_3") (pintype "bidirectional"))
    )
    (net (code "69") (name "unconnected-(U1-CPSA2{slash}VREF{slash}AN3{slash}RA3-Pad5)") (class "Default")
      (node (ref "U1") (pin "5") (pinfunction "CPSA2/VREF/AN3/RA3_5") (pintype "bidirectional"))
    )
    (net (code "70") (name "unconnected-(U1-RB1{slash}AN10{slash}CPSB9-Pad34)") (class "Default")
      (node (ref "U1") (pin "34") (pinfunction "RB1/AN10/CPSB9_34") (pintype "bidirectional"))
    )
    (net (code "71") (name "unconnected-(U1-RB2{slash}AN8{slash}CPSB10-Pad35)") (class "Default")
      (node (ref "U1") (pin "35") (pinfunction "RB2/AN8/CPSB10_35") (pintype "bidirectional"))
    )
    (net (code "72") (name "unconnected-(U1-RB3{slash}AN9{slash}CPSB11{slash}CCP2-Pad36)") (class "Default")
      (node (ref "U1") (pin "36") (pinfunction "RB3/AN9/CPSB11/CCP2_36") (pintype "bidirectional"))
    )
    (net (code "73") (name "unconnected-(U1-RB4{slash}AN11{slash}CPSB12-Pad37)") (class "Default")
      (node (ref "U1") (pin "37") (pinfunction "RB4/AN11/CPSB12_37") (pintype "bidirectional"))
    )
    (net (code "74") (name "unconnected-(U1-RB5{slash}AN13{slash}CPSB13{slash}T1G{slash}T3CKI-Pad38)") (class "Default")
      (node (ref "U1") (pin "38") (pinfunction "RB5/AN13/CPSB13/T1G/T3CKI_38") (pintype "bidirectional"))
    )
    (net (code "75") (name "unconnected-(U1-TACKI{slash}T0CKI{slash}CPSA3{slash}RA4-Pad6)") (class "Default")
      (node (ref "U1") (pin "6") (pinfunction "TACKI/T0CKI/CPSA3/RA4_6") (pintype "bidirectional"))
    )
    (net (code "76") (name "unconnected-(U1-VCAP{slash}CLKOUT{slash}OSC2{slash}CPSB1{slash}RA6-Pad14)") (class "Default")
      (node (ref "U1") (pin "14") (pinfunction "VCAP/CLKOUT/OSC2/CPSB1/RA6_14") (pintype "bidirectional"))
    )
    (net (code "77") (name "unconnected-(U1-VCAP{slash}~{SS}{slash}CPSA4{slash}AN4{slash}RA5-Pad7)") (class "Default")
      (node (ref "U1") (pin "7") (pinfunction "VCAP/~{SS}/CPSA4/AN4/RA5_7") (pintype "bidirectional"))
    )
    (net (code "78") (name "unconnected-(U4-PGD-Pad7)") (class "Default")
      (node (ref "U4") (pin "7") (pinfunction "PGD_7") (pintype "output"))
    )
    (net (code "79") (name "unconnected-(U4-VAUX-Pad2)") (class "Default")
      (node (ref "U4") (pin "2") (pinfunction "VAUX_2") (pintype "output"))
    )
    (net (code "80") (name "unconnected-(U4-VLDO-Pad6)") (class "Default")
      (node (ref "U4") (pin "6") (pinfunction "VLDO_6") (pintype "output"))
    )
    (net (code "81") (name "unconnected-(U4-VOUT-Pad4)") (class "Default")
      (node (ref "U4") (pin "4") (pinfunction "VOUT_4") (pintype "output"))
    )
    (net (code "82") (name "unconnected-(U4-VOUT2-Pad5)") (class "Default")
      (node (ref "U4") (pin "5") (pinfunction "VOUT2_5") (pintype "output"))
    )
    (net (code "83") (name "unconnected-(U4-VSTORE-Pad3)") (class "Default")
      (node (ref "U4") (pin "3") (pinfunction "VSTORE_3") (pintype "output"))
    )
    (net (code "84") (name "unconnected-(X1-Pad1)") (class "Default")
      (node (ref "X1") (pin "1") (pinfunction "1_1") (pintype "passive"))
    )
    (net (code "85") (name "unconnected-(X1-Pad4)") (class "Default")
      (node (ref "X1") (pin "4") (pinfunction "4_4") (pintype "passive"))
    )
    (net (code "86") (name "unconnected-(X1-Pad6)") (class "Default")
      (node (ref "X1") (pin "6") (pinfunction "6_6") (pintype "passive"))
    )
    (net (code "87") (name "unconnected-(X1-Pad7)") (class "Default")
      (node (ref "X1") (pin "7") (pinfunction "7_7") (pintype "passive"))
    )
    (net (code "88") (name "unconnected-(X1-Pad8)") (class "Default")
      (node (ref "X1") (pin "8") (pinfunction "8_8") (pintype "passive"))
    )
    (net (code "89") (name "unconnected-(X1-Pad9)") (class "Default")
      (node (ref "X1") (pin "9") (pinfunction "9_9") (pintype "passive"))
    )
    (net (code "90") (name "~{CHARGE_PULSE}") (class "Default")
      (node (ref "R14") (pin "P$2") (pinfunction "2_P$2") (pintype "passive"))
      (node (ref "U1") (pin "4") (pinfunction "DACOUT/CPSA1/AN2/RA2_4") (pintype "bidirectional"))
    )
    (net (code "91") (name "~{MCLR}") (class "Default")
      (node (ref "C1") (pin "1") (pinfunction "1_1") (pintype "passive"))
      (node (ref "J1") (pin "1") (pinfunction "VPP_1") (pintype "passive"))
      (node (ref "R1") (pin "P$1") (pinfunction "1_P$1") (pintype "passive"))
      (node (ref "S1") (pin "1") (pinfunction "S_1") (pintype "passive"))
      (node (ref "S1") (pin "2") (pinfunction "S1_2") (pintype "passive"))
      (node (ref "U1") (pin "1") (pinfunction "VPP/~{MCLR}/RE3_1") (pintype "input"))
    )
    (net (code "92") (name "~{VSUPERCAP_MEAS_EN}") (class "Default")
      (node (ref "U1") (pin "27") (pinfunction "RD4/CPSA12_27") (pintype "bidirectional"))
      (node (ref "U2") (pin "2") (pinfunction "G1_2") (pintype "input"))
    )
  )
)
